# odin_mod.net
KiCad netlist of a schematic drawn in EAGLE
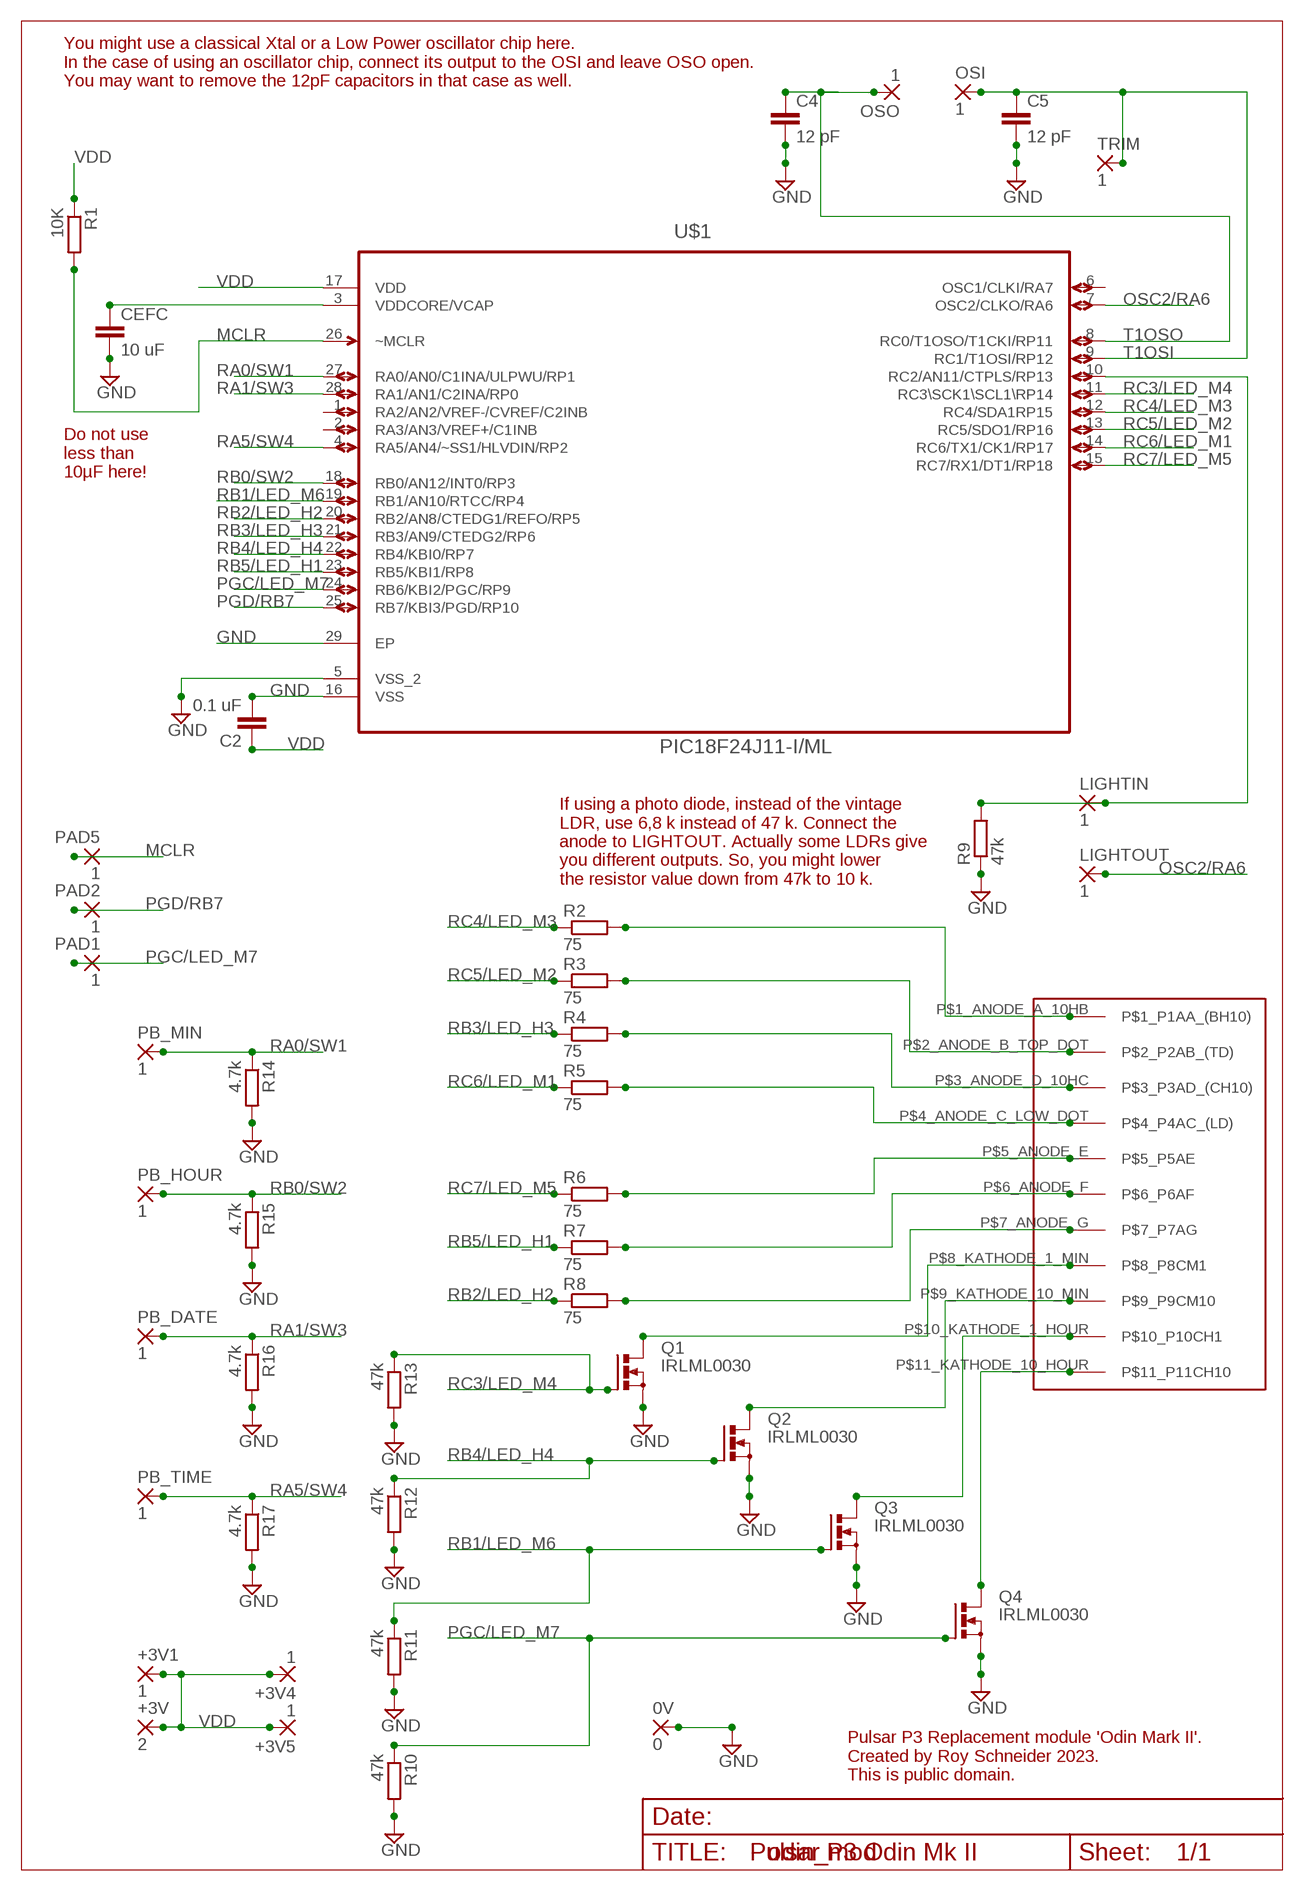
[diagram p0: schematic, sheet 1]

(export (version "E")
  (design (tool "Eeschema 10.0.6"))
  (components
    (comp (ref "+3V")
      (value "2")
      (footprint "eagle-import:SMD1,27-2,54")
      (libsource (lib "eagle-import") (part "SMD2"))
    )
    (comp (ref "+3V1")
      (value "1")
      (footprint "eagle-import:SMD1,27-2,54")
      (libsource (lib "eagle-import") (part "SMD2"))
    )
    (comp (ref "+3V4")
      (value "1")
      (footprint "eagle-import:SMD1,27-2,54")
      (libsource (lib "eagle-import") (part "SMD2"))
    )
    (comp (ref "+3V5")
      (value "1")
      (footprint "eagle-import:SMD1,27-2,54")
      (libsource (lib "eagle-import") (part "SMD2"))
    )
    (comp (ref "0V")
      (value "0")
      (footprint "eagle-import:SMD1,27-2,54")
      (libsource (lib "eagle-import") (part "SMD2"))
    )
    (comp (ref "C2")
      (value "0.1 uF")
      (footprint "eagle-import:C0603")
      (libsource (lib "eagle-import") (part "C-EUC0603"))
    )
    (comp (ref "C4")
      (value "12 pF")
      (footprint "eagle-import:C0603")
      (libsource (lib "eagle-import") (part "C-EUC0603"))
    )
    (comp (ref "C5")
      (value "12 pF")
      (footprint "eagle-import:C0603")
      (libsource (lib "eagle-import") (part "C-EUC0603"))
    )
    (comp (ref "CEFC")
      (value "10 uF")
      (footprint "eagle-import:C0603")
      (libsource (lib "eagle-import") (part "C-EUC0603"))
    )
    (comp (ref "LIGHTIN")
      (value "1")
      (footprint "eagle-import:SMD1,27-2,54")
      (libsource (lib "eagle-import") (part "SMD2"))
    )
    (comp (ref "LIGHTOUT")
      (value "1")
      (footprint "eagle-import:SMD1,27-2,54")
      (libsource (lib "eagle-import") (part "SMD2"))
    )
    (comp (ref "OSI")
      (value "1")
      (footprint "eagle-import:SMD1,27-2,54")
      (libsource (lib "eagle-import") (part "SMD2"))
    )
    (comp (ref "OSO")
      (value "1")
      (footprint "eagle-import:SMD1,27-2,54")
      (libsource (lib "eagle-import") (part "SMD2"))
    )
    (comp (ref "PAD1")
      (value "1")
      (footprint "eagle-import:SMD1,27-2,54")
      (libsource (lib "eagle-import") (part "SMD2"))
    )
    (comp (ref "PAD2")
      (value "1")
      (footprint "eagle-import:SMD1,27-2,54")
      (libsource (lib "eagle-import") (part "SMD2"))
    )
    (comp (ref "PAD5")
      (value "1")
      (footprint "eagle-import:SMD1,27-2,54")
      (libsource (lib "eagle-import") (part "SMD2"))
    )
    (comp (ref "PB_DATE")
      (value "1")
      (footprint "eagle-import:SMD1,27-2,54")
      (libsource (lib "eagle-import") (part "SMD2"))
    )
    (comp (ref "PB_HOUR")
      (value "1")
      (footprint "eagle-import:SMD1,27-2,54")
      (libsource (lib "eagle-import") (part "SMD2"))
    )
    (comp (ref "PB_MIN")
      (value "1")
      (footprint "eagle-import:SMD1,27-2,54")
      (libsource (lib "eagle-import") (part "SMD2"))
    )
    (comp (ref "PB_TIME")
      (value "1")
      (footprint "eagle-import:SMD1,27-2,54")
      (libsource (lib "eagle-import") (part "SMD2"))
    )
    (comp (ref "Q1")
      (value "IRLML0030")
      (footprint "eagle-import:SOT-23")
      (libsource (lib "eagle-import") (part "IRLML0030"))
    )
    (comp (ref "Q2")
      (value "IRLML0030")
      (footprint "eagle-import:SOT-23")
      (libsource (lib "eagle-import") (part "IRLML0030"))
    )
    (comp (ref "Q3")
      (value "IRLML0030")
      (footprint "eagle-import:SOT-23")
      (libsource (lib "eagle-import") (part "IRLML0030"))
    )
    (comp (ref "Q4")
      (value "IRLML0030")
      (footprint "eagle-import:SOT-23")
      (libsource (lib "eagle-import") (part "IRLML0030"))
    )
    (comp (ref "R1")
      (value "10K")
      (footprint "eagle-import:R0402")
      (libsource (lib "eagle-import") (part "R-EU_R0402"))
    )
    (comp (ref "R2")
      (value "75")
      (footprint "eagle-import:R0402")
      (libsource (lib "eagle-import") (part "resistor_R-EU_R0402"))
    )
    (comp (ref "R3")
      (value "75")
      (footprint "eagle-import:R0402")
      (libsource (lib "eagle-import") (part "resistor_R-EU_R0402"))
    )
    (comp (ref "R4")
      (value "75")
      (footprint "eagle-import:R0402")
      (libsource (lib "eagle-import") (part "resistor_R-EU_R0402"))
    )
    (comp (ref "R5")
      (value "75")
      (footprint "eagle-import:R0402")
      (libsource (lib "eagle-import") (part "resistor_R-EU_R0402"))
    )
    (comp (ref "R6")
      (value "75")
      (footprint "eagle-import:R0402")
      (libsource (lib "eagle-import") (part "resistor_R-EU_R0402"))
    )
    (comp (ref "R7")
      (value "75")
      (footprint "eagle-import:R0402")
      (libsource (lib "eagle-import") (part "resistor_R-EU_R0402"))
    )
    (comp (ref "R8")
      (value "75")
      (footprint "eagle-import:R0402")
      (libsource (lib "eagle-import") (part "resistor_R-EU_R0402"))
    )
    (comp (ref "R9")
      (value "47k")
      (footprint "eagle-import:R0402")
      (libsource (lib "eagle-import") (part "resistor_R-EU_R0402"))
    )
    (comp (ref "R10")
      (value "47k")
      (footprint "eagle-import:R0402")
      (libsource (lib "eagle-import") (part "resistor_R-EU_R0402"))
    )
    (comp (ref "R11")
      (value "47k")
      (footprint "eagle-import:R0402")
      (libsource (lib "eagle-import") (part "resistor_R-EU_R0402"))
    )
    (comp (ref "R12")
      (value "47k")
      (footprint "eagle-import:R0402")
      (libsource (lib "eagle-import") (part "resistor_R-EU_R0402"))
    )
    (comp (ref "R13")
      (value "47k")
      (footprint "eagle-import:R0402")
      (libsource (lib "eagle-import") (part "resistor_R-EU_R0402"))
    )
    (comp (ref "R14")
      (value "4.7k")
      (footprint "eagle-import:R0402")
      (libsource (lib "eagle-import") (part "resistor_R-EU_R0402"))
    )
    (comp (ref "R15")
      (value "4.7k")
      (footprint "eagle-import:R0402")
      (libsource (lib "eagle-import") (part "resistor_R-EU_R0402"))
    )
    (comp (ref "R16")
      (value "4.7k")
      (footprint "eagle-import:R0402")
      (libsource (lib "eagle-import") (part "resistor_R-EU_R0402"))
    )
    (comp (ref "R17")
      (value "4.7k")
      (footprint "eagle-import:R0402")
      (libsource (lib "eagle-import") (part "resistor_R-EU_R0402"))
    )
    (comp (ref "TRIM")
      (value "1")
      (footprint "eagle-import:SMD1,27-2,54")
      (libsource (lib "eagle-import") (part "SMD2"))
    )
    (comp (ref "U$1")
      (value "PIC18F24J11-I/ML")
      (footprint "eagle-import:QFN65P600X600X100-29N")
      (fields (field (name "MPN") "PIC18F24J11-I/Ml"))
      (libsource (lib "eagle-import") (part "PIC18F24J11-I/ML"))
    )
    (comp (ref "U$3")
      (value "PULSAR_P3_DISPLAY")
      (footprint "eagle-import:PULSAR_P3_LED_DISPLAY")
      (libsource (lib "eagle-import") (part "PULSAR_P3_DISPLAY"))
    )
  )
  (nets
    (net (code "1") (name "/MCLR") (class "Default")
      (node (ref "PAD5") (pin "1") (pinfunction "P_1") (pintype "passive"))
      (node (ref "R1") (pin "2") (pinfunction "2_2") (pintype "passive"))
      (node (ref "U$1") (pin "26") (pinfunction "~{MCLR}_26") (pintype "input"))
    )
    (net (code "2") (name "/OSC2{slash}RA6") (class "Default")
      (node (ref "LIGHTOUT") (pin "1") (pinfunction "P_1") (pintype "passive"))
      (node (ref "U$1") (pin "7") (pinfunction "OSC2/CLKO/RA6_7") (pintype "bidirectional"))
    )
    (net (code "3") (name "/PGC{slash}LED_M7") (class "Default")
      (node (ref "PAD1") (pin "1") (pinfunction "P_1") (pintype "passive"))
      (node (ref "Q4") (pin "P1") (pinfunction "G_P1") (pintype "passive"))
      (node (ref "R10") (pin "1") (pinfunction "1_1") (pintype "passive"))
      (node (ref "U$1") (pin "24") (pinfunction "RB6/KBI2/PGC/RP9_24") (pintype "bidirectional"))
    )
    (net (code "4") (name "/PGD{slash}RB7") (class "Default")
      (node (ref "PAD2") (pin "1") (pinfunction "P_1") (pintype "passive"))
      (node (ref "U$1") (pin "25") (pinfunction "RB7/KBI3/PGD/RP10_25") (pintype "bidirectional"))
    )
    (net (code "5") (name "/RA0{slash}SW1") (class "Default")
      (node (ref "PB_MIN") (pin "1") (pinfunction "P_1") (pintype "passive"))
      (node (ref "R14") (pin "1") (pinfunction "1_1") (pintype "passive"))
      (node (ref "U$1") (pin "27") (pinfunction "RA0/AN0/C1INA/ULPWU/RP1_27") (pintype "bidirectional"))
    )
    (net (code "6") (name "/RA1{slash}SW3") (class "Default")
      (node (ref "PB_DATE") (pin "1") (pinfunction "P_1") (pintype "passive"))
      (node (ref "R16") (pin "1") (pinfunction "1_1") (pintype "passive"))
      (node (ref "U$1") (pin "28") (pinfunction "RA1/AN1/C2INA/RP0_28") (pintype "bidirectional"))
    )
    (net (code "7") (name "/RA5{slash}SW4") (class "Default")
      (node (ref "PB_TIME") (pin "1") (pinfunction "P_1") (pintype "passive"))
      (node (ref "R17") (pin "1") (pinfunction "1_1") (pintype "passive"))
      (node (ref "U$1") (pin "4") (pinfunction "RA5/AN4/~{SS1/HLVDIN/RP2}_4") (pintype "bidirectional"))
    )
    (net (code "8") (name "/RB0{slash}SW2") (class "Default")
      (node (ref "PB_HOUR") (pin "1") (pinfunction "P_1") (pintype "passive"))
      (node (ref "R15") (pin "1") (pinfunction "1_1") (pintype "passive"))
      (node (ref "U$1") (pin "18") (pinfunction "RB0/AN12/INT0/RP3_18") (pintype "bidirectional"))
    )
    (net (code "9") (name "/RB1{slash}LED_M6") (class "Default")
      (node (ref "Q3") (pin "P1") (pinfunction "G_P1") (pintype "passive"))
      (node (ref "R11") (pin "1") (pinfunction "1_1") (pintype "passive"))
      (node (ref "U$1") (pin "19") (pinfunction "RB1/AN10/RTCC/RP4_19") (pintype "bidirectional"))
    )
    (net (code "10") (name "/RB2{slash}LED_H2") (class "Default")
      (node (ref "R8") (pin "1") (pinfunction "1_1") (pintype "passive"))
      (node (ref "U$1") (pin "20") (pinfunction "RB2/AN8/CTEDG1/REFO/RP5_20") (pintype "bidirectional"))
    )
    (net (code "11") (name "/RB3{slash}LED_H3") (class "Default")
      (node (ref "R4") (pin "1") (pinfunction "1_1") (pintype "passive"))
      (node (ref "U$1") (pin "21") (pinfunction "RB3/AN9/CTEDG2/RP6_21") (pintype "bidirectional"))
    )
    (net (code "12") (name "/RB4{slash}LED_H4") (class "Default")
      (node (ref "Q2") (pin "P1") (pinfunction "G_P1") (pintype "passive"))
      (node (ref "R12") (pin "1") (pinfunction "1_1") (pintype "passive"))
      (node (ref "U$1") (pin "22") (pinfunction "RB4/KBI0/RP7_22") (pintype "bidirectional"))
    )
    (net (code "13") (name "/RB5{slash}LED_H1") (class "Default")
      (node (ref "R7") (pin "1") (pinfunction "1_1") (pintype "passive"))
      (node (ref "U$1") (pin "23") (pinfunction "RB5/KBI1/RP8_23") (pintype "bidirectional"))
    )
    (net (code "14") (name "/RC3{slash}LED_M4") (class "Default")
      (node (ref "Q1") (pin "P1") (pinfunction "G_P1") (pintype "passive"))
      (node (ref "R13") (pin "1") (pinfunction "1_1") (pintype "passive"))
      (node (ref "U$1") (pin "11") (pinfunction "RC3\\SCK1\\SCL1\\RP14_11") (pintype "bidirectional"))
    )
    (net (code "15") (name "/RC4{slash}LED_M3") (class "Default")
      (node (ref "R2") (pin "1") (pinfunction "1_1") (pintype "passive"))
      (node (ref "U$1") (pin "12") (pinfunction "RC4/SDA1RP15_12") (pintype "bidirectional"))
    )
    (net (code "16") (name "/RC5{slash}LED_M2") (class "Default")
      (node (ref "R3") (pin "1") (pinfunction "1_1") (pintype "passive"))
      (node (ref "U$1") (pin "13") (pinfunction "RC5/SDO1/RP16_13") (pintype "bidirectional"))
    )
    (net (code "17") (name "/RC6{slash}LED_M1") (class "Default")
      (node (ref "R5") (pin "1") (pinfunction "1_1") (pintype "passive"))
      (node (ref "U$1") (pin "14") (pinfunction "RC6/TX1/CK1/RP17_14") (pintype "bidirectional"))
    )
    (net (code "18") (name "/RC7{slash}LED_M5") (class "Default")
      (node (ref "R6") (pin "1") (pinfunction "1_1") (pintype "passive"))
      (node (ref "U$1") (pin "15") (pinfunction "RC7/RX1/DT1/RP18_15") (pintype "bidirectional"))
    )
    (net (code "19") (name "/T1OSI") (class "Default")
      (node (ref "C5") (pin "1") (pinfunction "1_1") (pintype "passive"))
      (node (ref "OSI") (pin "1") (pinfunction "P_1") (pintype "passive"))
      (node (ref "TRIM") (pin "1") (pinfunction "P_1") (pintype "passive"))
      (node (ref "U$1") (pin "9") (pinfunction "RC1/T1OSI/RP12_9") (pintype "bidirectional"))
    )
    (net (code "20") (name "/T1OSO") (class "Default")
      (node (ref "C4") (pin "1") (pinfunction "1_1") (pintype "passive"))
      (node (ref "OSO") (pin "1") (pinfunction "P_1") (pintype "passive"))
      (node (ref "U$1") (pin "8") (pinfunction "RC0/T1OSO/T1CKI/RP11_8") (pintype "bidirectional"))
    )
    (net (code "21") (name "/VDD") (class "Default")
      (node (ref "+3V") (pin "1") (pinfunction "P_1") (pintype "passive"))
      (node (ref "+3V1") (pin "1") (pinfunction "P_1") (pintype "passive"))
      (node (ref "+3V4") (pin "1") (pinfunction "P_1") (pintype "passive"))
      (node (ref "+3V5") (pin "1") (pinfunction "P_1") (pintype "passive"))
      (node (ref "C2") (pin "1") (pinfunction "1_1") (pintype "passive"))
      (node (ref "R1") (pin "1") (pinfunction "1_1") (pintype "passive"))
      (node (ref "U$1") (pin "17") (pinfunction "VDD_17") (pintype "power_in"))
    )
    (net (code "22") (name "GND") (class "Default")
      (node (ref "0V") (pin "1") (pinfunction "P_1") (pintype "passive"))
      (node (ref "C2") (pin "2") (pinfunction "2_2") (pintype "passive"))
      (node (ref "C4") (pin "2") (pinfunction "2_2") (pintype "passive"))
      (node (ref "C5") (pin "2") (pinfunction "2_2") (pintype "passive"))
      (node (ref "CEFC") (pin "2") (pinfunction "2_2") (pintype "passive"))
      (node (ref "Q1") (pin "P2") (pinfunction "S_P2") (pintype "passive"))
      (node (ref "Q2") (pin "P2") (pinfunction "S_P2") (pintype "passive"))
      (node (ref "Q3") (pin "P2") (pinfunction "S_P2") (pintype "passive"))
      (node (ref "Q4") (pin "P2") (pinfunction "S_P2") (pintype "passive"))
      (node (ref "R10") (pin "2") (pinfunction "2_2") (pintype "passive"))
      (node (ref "R11") (pin "2") (pinfunction "2_2") (pintype "passive"))
      (node (ref "R12") (pin "2") (pinfunction "2_2") (pintype "passive"))
      (node (ref "R13") (pin "2") (pinfunction "2_2") (pintype "passive"))
      (node (ref "R14") (pin "2") (pinfunction "2_2") (pintype "passive"))
      (node (ref "R15") (pin "2") (pinfunction "2_2") (pintype "passive"))
      (node (ref "R16") (pin "2") (pinfunction "2_2") (pintype "passive"))
      (node (ref "R17") (pin "2") (pinfunction "2_2") (pintype "passive"))
      (node (ref "R9") (pin "1") (pinfunction "1_1") (pintype "passive"))
      (node (ref "U$1") (pin "16") (pinfunction "VSS_16") (pintype "passive"))
      (node (ref "U$1") (pin "29") (pinfunction "EP_29") (pintype "passive"))
      (node (ref "U$1") (pin "5") (pinfunction "VSS_2_5") (pintype "passive"))
    )
    (net (code "23") (name "Net-(LIGHTIN-P)") (class "Default")
      (node (ref "LIGHTIN") (pin "1") (pinfunction "P_1") (pintype "passive"))
      (node (ref "R9") (pin "2") (pinfunction "2_2") (pintype "passive"))
      (node (ref "U$1") (pin "10") (pinfunction "RC2/AN11/CTPLS/RP13_10") (pintype "bidirectional"))
    )
    (net (code "24") (name "Net-(Q1-D)") (class "Default")
      (node (ref "Q1") (pin "P3") (pinfunction "D_P3") (pintype "passive"))
      (node (ref "U$3") (pin "P$8_KATHODE_1_MIN") (pinfunction "P$8_P8CM1_P$8_KATHODE_1_MIN") (pintype "bidirectional"))
    )
    (net (code "25") (name "Net-(Q2-D)") (class "Default")
      (node (ref "Q2") (pin "P3") (pinfunction "D_P3") (pintype "passive"))
      (node (ref "U$3") (pin "P$9_KATHODE_10_MIN") (pinfunction "P$9_P9CM10_P$9_KATHODE_10_MIN") (pintype "bidirectional"))
    )
    (net (code "26") (name "Net-(Q3-D)") (class "Default")
      (node (ref "Q3") (pin "P3") (pinfunction "D_P3") (pintype "passive"))
      (node (ref "U$3") (pin "P$10_KATHODE_1_HOUR") (pinfunction "P$10_P10CH1_P$10_KATHODE_1_HOUR") (pintype "bidirectional"))
    )
    (net (code "27") (name "Net-(Q4-D)") (class "Default")
      (node (ref "Q4") (pin "P3") (pinfunction "D_P3") (pintype "passive"))
      (node (ref "U$3") (pin "P$11_KATHODE_10_HOUR") (pinfunction "P$11_P11CH10_P$11_KATHODE_10_HOUR") (pintype "bidirectional"))
    )
    (net (code "28") (name "Net-(U$1-VDDCORE{slash}VCAP)") (class "Default")
      (node (ref "CEFC") (pin "1") (pinfunction "1_1") (pintype "passive"))
      (node (ref "U$1") (pin "3") (pinfunction "VDDCORE/VCAP_3") (pintype "power_in"))
    )
    (net (code "29") (name "Net-(U$3-P$1_P1AA_(BH10))") (class "Default")
      (node (ref "R2") (pin "2") (pinfunction "2_2") (pintype "passive"))
      (node (ref "U$3") (pin "P$1_ANODE_A_10HB") (pinfunction "P$1_P1AA_(BH10)_P$1_ANODE_A_10HB") (pintype "bidirectional"))
    )
    (net (code "30") (name "Net-(U$3-P$2_P2AB_(TD))") (class "Default")
      (node (ref "R3") (pin "2") (pinfunction "2_2") (pintype "passive"))
      (node (ref "U$3") (pin "P$2_ANODE_B_TOP_DOT") (pinfunction "P$2_P2AB_(TD)_P$2_ANODE_B_TOP_DOT") (pintype "bidirectional"))
    )
    (net (code "31") (name "Net-(U$3-P$3_P3AD_(CH10))") (class "Default")
      (node (ref "R4") (pin "2") (pinfunction "2_2") (pintype "passive"))
      (node (ref "U$3") (pin "P$3_ANODE_D_10HC") (pinfunction "P$3_P3AD_(CH10)_P$3_ANODE_D_10HC") (pintype "bidirectional"))
    )
    (net (code "32") (name "Net-(U$3-P$4_P4AC_(LD))") (class "Default")
      (node (ref "R5") (pin "2") (pinfunction "2_2") (pintype "passive"))
      (node (ref "U$3") (pin "P$4_ANODE_C_LOW_DOT") (pinfunction "P$4_P4AC_(LD)_P$4_ANODE_C_LOW_DOT") (pintype "bidirectional"))
    )
    (net (code "33") (name "Net-(U$3-P$5_P5AE)") (class "Default")
      (node (ref "R6") (pin "2") (pinfunction "2_2") (pintype "passive"))
      (node (ref "U$3") (pin "P$5_ANODE_E") (pinfunction "P$5_P5AE_P$5_ANODE_E") (pintype "bidirectional"))
    )
    (net (code "34") (name "Net-(U$3-P$6_P6AF)") (class "Default")
      (node (ref "R7") (pin "2") (pinfunction "2_2") (pintype "passive"))
      (node (ref "U$3") (pin "P$6_ANODE_F") (pinfunction "P$6_P6AF_P$6_ANODE_F") (pintype "bidirectional"))
    )
    (net (code "35") (name "Net-(U$3-P$7_P7AG)") (class "Default")
      (node (ref "R8") (pin "2") (pinfunction "2_2") (pintype "passive"))
      (node (ref "U$3") (pin "P$7_ANODE_G") (pinfunction "P$7_P7AG_P$7_ANODE_G") (pintype "bidirectional"))
    )
    (net (code "36") (name "unconnected-(U$1-OSC1{slash}CLKI{slash}RA7-Pad6)") (class "Default")
      (node (ref "U$1") (pin "6") (pinfunction "OSC1/CLKI/RA7_6") (pintype "bidirectional"))
    )
    (net (code "37") (name "unconnected-(U$1-RA2{slash}AN2{slash}VREF-{slash}CVREF{slash}C2INB-Pad1)") (class "Default")
      (node (ref "U$1") (pin "1") (pinfunction "RA2/AN2/VREF-/CVREF/C2INB_1") (pintype "bidirectional"))
    )
    (net (code "38") (name "unconnected-(U$1-RA3{slash}AN3{slash}VREF+{slash}C1INB-Pad2)") (class "Default")
      (node (ref "U$1") (pin "2") (pinfunction "RA3/AN3/VREF+/C1INB_2") (pintype "bidirectional"))
    )
  )
)
